# detector-opamp.net
KiCad netlist of a schematic drawn in EAGLE
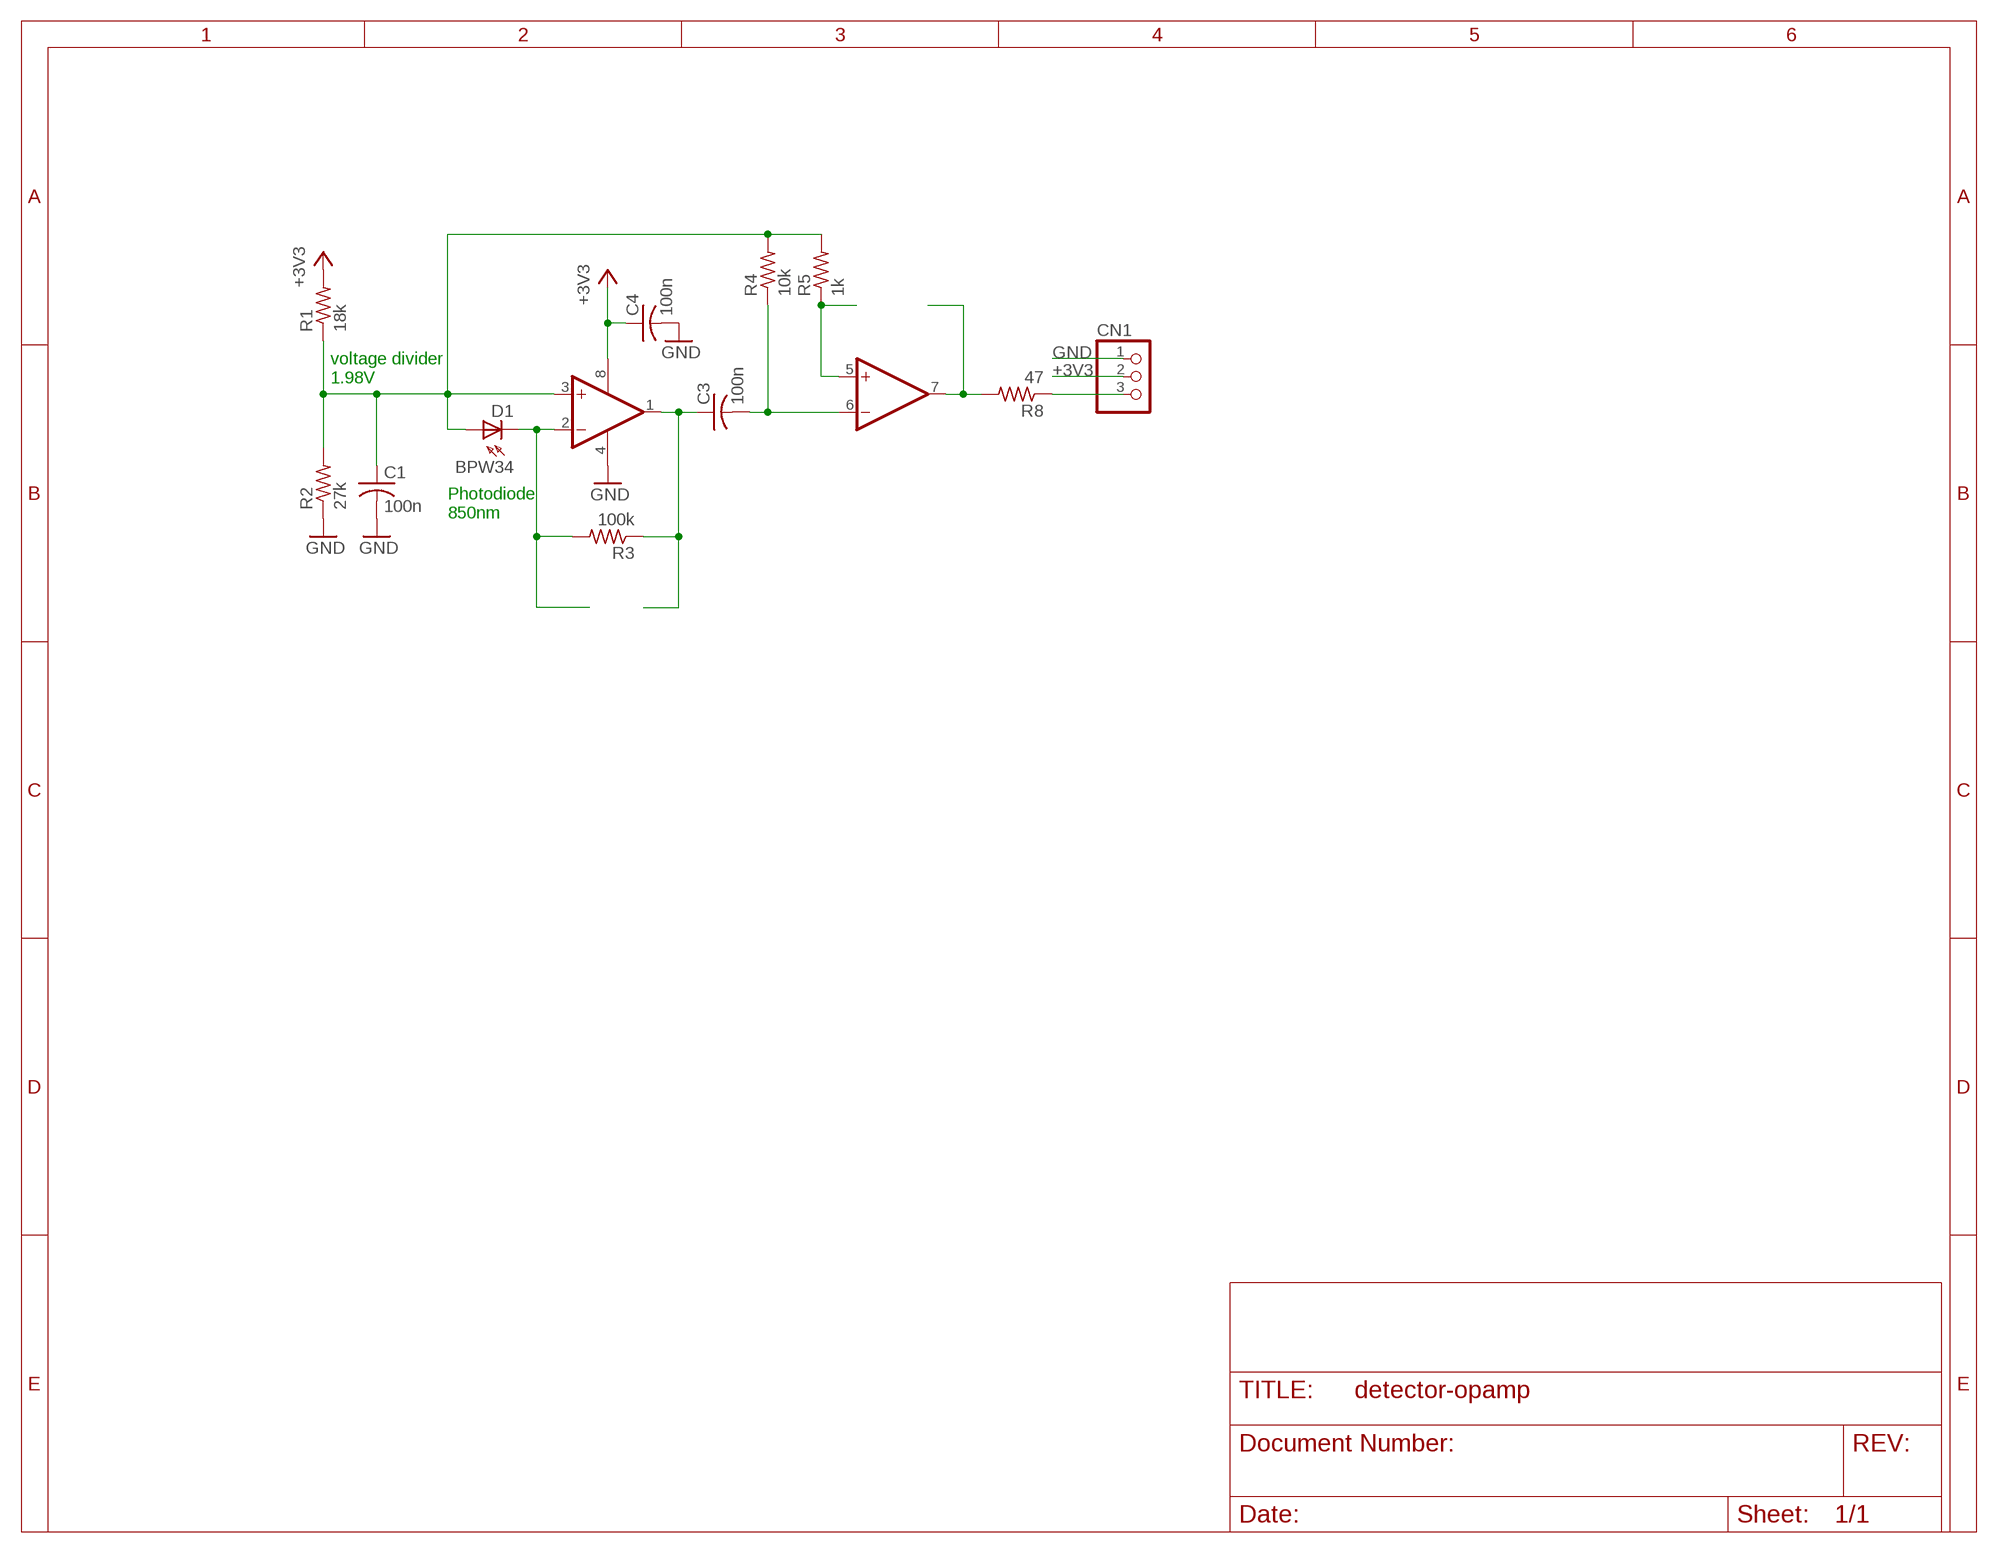
[diagram p0: schematic, sheet 1]

(export (version "E")
  (design (tool "Eeschema 10.0.6"))
  (components
    (comp (ref "C1")
      (value "100n")
      (footprint "eagle-import:C0603K")
      (libsource (lib "eagle-import") (part "C-USC0603K"))
    )
    (comp (ref "C3")
      (value "100n")
      (footprint "eagle-import:C0603K")
      (libsource (lib "eagle-import") (part "C-USC0603K"))
    )
    (comp (ref "C4")
      (value "100n")
      (footprint "eagle-import:C0603K")
      (libsource (lib "eagle-import") (part "C-USC0603K"))
    )
    (comp (ref "CN1")
      (value "JST_3PIN")
      (footprint "eagle-import:JSTPH3")
      (libsource (lib "eagle-import") (part "JST_3PIN"))
    )
    (comp (ref "D1")
      (value "BPW34")
      (footprint "eagle-import:BPW32")
      (libsource (lib "eagle-import") (part "BPW32"))
    )
    (comp (ref "IC1")
      (value "OPA2725D")
      (footprint "eagle-import:SO08")
      (libsource (lib "eagle-import") (part "OPA2725D"))
    )
    (comp (ref "R1")
      (value "18k")
      (footprint "eagle-import:R0402")
      (libsource (lib "eagle-import") (part "R-US_R0402"))
    )
    (comp (ref "R2")
      (value "27k")
      (footprint "eagle-import:R0402")
      (libsource (lib "eagle-import") (part "R-US_R0402"))
    )
    (comp (ref "R3")
      (value "100k")
      (footprint "eagle-import:R0402")
      (libsource (lib "eagle-import") (part "R-US_R0402"))
    )
    (comp (ref "R4")
      (value "10k")
      (footprint "eagle-import:R0402")
      (libsource (lib "eagle-import") (part "R-US_R0402"))
    )
    (comp (ref "R5")
      (value "1k")
      (footprint "eagle-import:R0402")
      (libsource (lib "eagle-import") (part "R-US_R0402"))
    )
    (comp (ref "R8")
      (value "47")
      (footprint "eagle-import:R0402")
      (libsource (lib "eagle-import") (part "R-US_R0402"))
    )
  )
  (nets
    (net (code "1") (name "+3V3") (class "Default")
      (node (ref "C4") (pin "1") (pinfunction "1_1") (pintype "passive"))
      (node (ref "CN1") (pin "2") (pinfunction "2_2") (pintype "passive"))
      (node (ref "IC1") (pin "8") (pinfunction "V+_8") (pintype "power_in"))
      (node (ref "R1") (pin "2") (pinfunction "2_2") (pintype "passive"))
    )
    (net (code "2") (name "GND") (class "Default")
      (node (ref "C1") (pin "2") (pinfunction "2_2") (pintype "passive"))
      (node (ref "C4") (pin "2") (pinfunction "2_2") (pintype "passive"))
      (node (ref "CN1") (pin "1") (pinfunction "1_1") (pintype "passive"))
      (node (ref "IC1") (pin "4") (pinfunction "V-_4") (pintype "power_in"))
      (node (ref "R2") (pin "1") (pinfunction "1_1") (pintype "passive"))
    )
    (net (code "3") (name "Net-(CN1-Pad3)") (class "Default")
      (node (ref "CN1") (pin "3") (pinfunction "3_3") (pintype "passive"))
      (node (ref "R8") (pin "1") (pinfunction "1_1") (pintype "passive"))
    )
    (net (code "4") (name "Net-(D1-C)") (class "Default")
      (node (ref "D1") (pin "K") (pinfunction "C_K") (pintype "passive"))
      (node (ref "IC1") (pin "2") (pinfunction "-IN_2") (pintype "input"))
      (node (ref "R3") (pin "2") (pinfunction "2_2") (pintype "passive"))
    )
    (net (code "5") (name "Net-(IC1A-+IN)") (class "Default")
      (node (ref "C1") (pin "1") (pinfunction "1_1") (pintype "passive"))
      (node (ref "D1") (pin "A") (pinfunction "A_A") (pintype "passive"))
      (node (ref "IC1") (pin "3") (pinfunction "+IN_3") (pintype "input"))
      (node (ref "R1") (pin "1") (pinfunction "1_1") (pintype "passive"))
      (node (ref "R2") (pin "2") (pinfunction "2_2") (pintype "passive"))
      (node (ref "R4") (pin "2") (pinfunction "2_2") (pintype "passive"))
      (node (ref "R5") (pin "2") (pinfunction "2_2") (pintype "passive"))
    )
    (net (code "6") (name "Net-(IC1A-OUT)") (class "Default")
      (node (ref "C3") (pin "1") (pinfunction "1_1") (pintype "passive"))
      (node (ref "IC1") (pin "1") (pinfunction "OUT_1") (pintype "output"))
      (node (ref "R3") (pin "1") (pinfunction "1_1") (pintype "passive"))
    )
    (net (code "7") (name "Net-(IC1B-+IN)") (class "Default")
      (node (ref "IC1") (pin "5") (pinfunction "+IN_5") (pintype "input"))
      (node (ref "R5") (pin "1") (pinfunction "1_1") (pintype "passive"))
    )
    (net (code "8") (name "Net-(IC1B--IN)") (class "Default")
      (node (ref "C3") (pin "2") (pinfunction "2_2") (pintype "passive"))
      (node (ref "IC1") (pin "6") (pinfunction "-IN_6") (pintype "input"))
      (node (ref "R4") (pin "1") (pinfunction "1_1") (pintype "passive"))
    )
    (net (code "9") (name "Net-(IC1B-OUT)") (class "Default")
      (node (ref "IC1") (pin "7") (pinfunction "OUT_7") (pintype "output"))
      (node (ref "R8") (pin "2") (pinfunction "2_2") (pintype "passive"))
    )
  )
)
